# Led_7_dig_display.net
KiCad netlist of a schematic drawn in Altium Designer
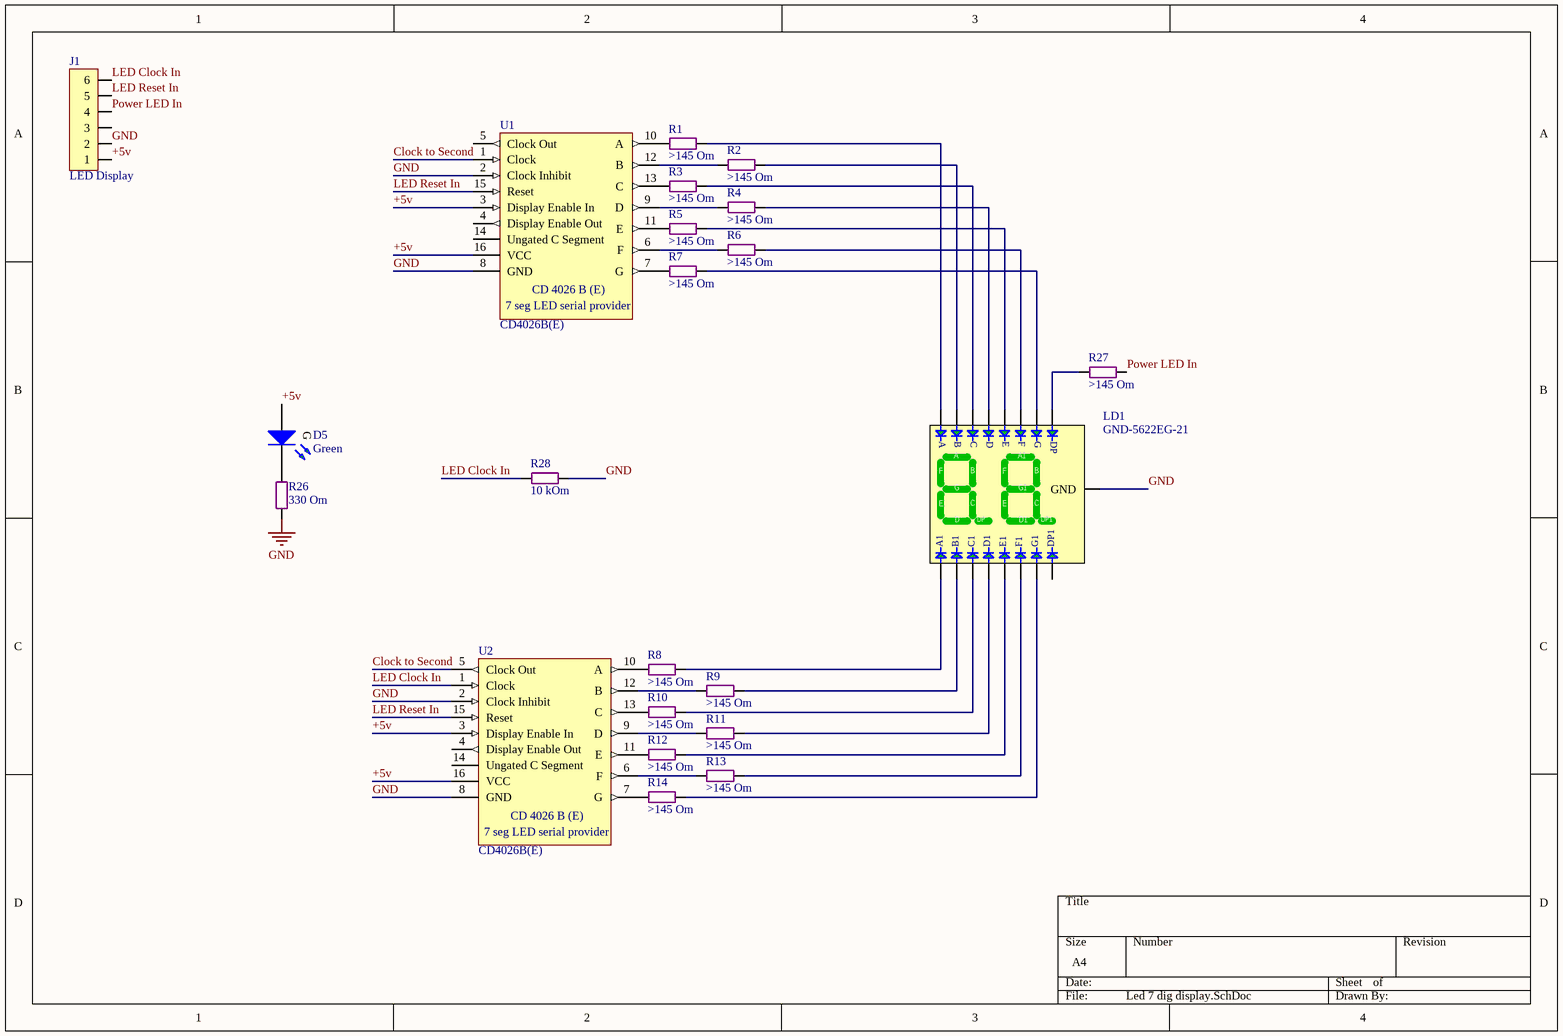
[diagram p0: Led 7 dig display.SchDoc]

(export (version "E")
  (design (tool "Eeschema 10.0.6"))
  (components
    (comp (ref "D5")
      (value "Green")
      (footprint "LED:LED SMD 0805 Green")
      (description "?2v ?20mA")
      (libsource (lib "LED") (part "Led SMD 0805 Green"))
    )
    (comp (ref "J1")
      (value "LED Display")
      (footprint "Connector:Molex Micro-Fit 3.0 - 6 pin D R")
      (description "Horisontal, Dbl line, Male - 3mm")
      (libsource (lib "Connector") (part "Micro-Fit 6R (2x3)"))
    )
    (comp (ref "LD1")
      (value "GND-5622EG-21")
      (footprint "LED:GND-5622EG-21")
      (description "Green, Common Catode 2 Digits")
      (libsource (lib "LED") (part "7 Seg GND-5622EG-21"))
    )
    (comp (ref "R1")
      (value ">145 Om")
      (footprint "PassiveComponents:SMD 1206 (3216)")
      (libsource (lib "PassiveComponents") (part "Res All Types"))
    )
    (comp (ref "R2")
      (value ">145 Om")
      (footprint "PassiveComponents:SMD 1206 (3216)")
      (libsource (lib "PassiveComponents") (part "Res All Types"))
    )
    (comp (ref "R3")
      (value ">145 Om")
      (footprint "PassiveComponents:SMD 1206 (3216)")
      (libsource (lib "PassiveComponents") (part "Res All Types"))
    )
    (comp (ref "R4")
      (value ">145 Om")
      (footprint "PassiveComponents:SMD 1206 (3216)")
      (libsource (lib "PassiveComponents") (part "Res All Types"))
    )
    (comp (ref "R5")
      (value ">145 Om")
      (footprint "PassiveComponents:SMD 1206 (3216)")
      (libsource (lib "PassiveComponents") (part "Res All Types"))
    )
    (comp (ref "R6")
      (value ">145 Om")
      (footprint "PassiveComponents:Res p7.62 (4p) 0.25w")
      (libsource (lib "PassiveComponents") (part "Res All Types"))
    )
    (comp (ref "R7")
      (value ">145 Om")
      (footprint "PassiveComponents:Res p7.62 (4p) 0.25w")
      (libsource (lib "PassiveComponents") (part "Res All Types"))
    )
    (comp (ref "R8")
      (value ">145 Om")
      (footprint "PassiveComponents:SMD 1206 (3216)")
      (libsource (lib "PassiveComponents") (part "Res All Types"))
    )
    (comp (ref "R9")
      (value ">145 Om")
      (footprint "PassiveComponents:Res p7.62 (4p) 0.25w")
      (libsource (lib "PassiveComponents") (part "Res All Types"))
    )
    (comp (ref "R10")
      (value ">145 Om")
      (footprint "PassiveComponents:SMD 1206 (3216)")
      (libsource (lib "PassiveComponents") (part "Res All Types"))
    )
    (comp (ref "R11")
      (value ">145 Om")
      (footprint "PassiveComponents:SMD 1206 (3216)")
      (libsource (lib "PassiveComponents") (part "Res All Types"))
    )
    (comp (ref "R12")
      (value ">145 Om")
      (footprint "PassiveComponents:SMD 1206 (3216)")
      (libsource (lib "PassiveComponents") (part "Res All Types"))
    )
    (comp (ref "R13")
      (value ">145 Om")
      (footprint "PassiveComponents:SMD 1206 (3216)")
      (libsource (lib "PassiveComponents") (part "Res All Types"))
    )
    (comp (ref "R14")
      (value ">145 Om")
      (footprint "PassiveComponents:Res p7.62 (4p) 0.25w")
      (libsource (lib "PassiveComponents") (part "Res All Types"))
    )
    (comp (ref "R26")
      (value "330 Om")
      (footprint "PassiveComponents:SMD 1206 (3216)")
      (libsource (lib "PassiveComponents") (part "Res All Types"))
    )
    (comp (ref "R27")
      (value ">145 Om")
      (footprint "PassiveComponents:SMD 1206 (3216)")
      (libsource (lib "PassiveComponents") (part "Res SMD 1206"))
    )
    (comp (ref "R28")
      (value "10 kOm")
      (footprint "PassiveComponents:SMD 0805 (2012)")
      (libsource (lib "PassiveComponents") (part "Res All Types"))
    )
    (comp (ref "U1")
      (value "CD4026B(E)")
      (footprint "GeneralCases:DIP-16")
      (description "jk Trigger")
      (libsource (lib "Chips") (part "CD4026BE"))
    )
    (comp (ref "U2")
      (value "CD4026B(E)")
      (footprint "GeneralCases:DIP-16")
      (description "jk Trigger")
      (libsource (lib "Chips") (part "CD4026BE"))
    )
  )
  (nets
    (net (code "1") (name "/+5v") (class "Default")
      (node (ref "D5") (pin "A") (pinfunction "A_A") (pintype "passive"))
      (node (ref "J1") (pin "1") (pinfunction "1_1") (pintype "passive"))
      (node (ref "U1") (pin "16") (pinfunction "VCC_16") (pintype "power_in"))
      (node (ref "U1") (pin "3") (pinfunction "Display_Enable_In_3") (pintype "input"))
      (node (ref "U2") (pin "16") (pinfunction "VCC_16") (pintype "power_in"))
      (node (ref "U2") (pin "3") (pinfunction "Display_Enable_In_3") (pintype "input"))
    )
    (net (code "2") (name "/Clock to Second") (class "Default")
      (node (ref "U1") (pin "1") (pinfunction "Clock_1") (pintype "input"))
      (node (ref "U2") (pin "5") (pinfunction "Clock_Out_5") (pintype "output"))
    )
    (net (code "3") (name "/LED Clock In") (class "Default")
      (node (ref "J1") (pin "6") (pinfunction "6_6") (pintype "passive"))
      (node (ref "R28") (pin "1") (pinfunction "1_1") (pintype "passive"))
      (node (ref "U2") (pin "1") (pinfunction "Clock_1") (pintype "input"))
    )
    (net (code "4") (name "/LED Reset In") (class "Default")
      (node (ref "J1") (pin "5") (pinfunction "5_5") (pintype "passive"))
      (node (ref "U1") (pin "15") (pinfunction "Reset_15") (pintype "input"))
      (node (ref "U2") (pin "15") (pinfunction "Reset_15") (pintype "input"))
    )
    (net (code "5") (name "/Power LED In") (class "Default")
      (node (ref "J1") (pin "4") (pinfunction "4_4") (pintype "passive"))
      (node (ref "R27") (pin "2") (pinfunction "2_2") (pintype "passive"))
    )
    (net (code "6") (name "GND") (class "Default")
      (node (ref "J1") (pin "2") (pinfunction "2_2") (pintype "passive"))
      (node (ref "LD1") (pin "GND") (pinfunction "GND_GND") (pintype "passive"))
      (node (ref "R26") (pin "2") (pinfunction "2_2") (pintype "passive"))
      (node (ref "R28") (pin "2") (pinfunction "2_2") (pintype "passive"))
      (node (ref "U1") (pin "2") (pinfunction "Clock_Inhibit_2") (pintype "input"))
      (node (ref "U1") (pin "8") (pinfunction "GND_8") (pintype "power_in"))
      (node (ref "U2") (pin "2") (pinfunction "Clock_Inhibit_2") (pintype "input"))
      (node (ref "U2") (pin "8") (pinfunction "GND_8") (pintype "power_in"))
    )
    (net (code "7") (name "Net-(D5-PadK)") (class "Default")
      (node (ref "D5") (pin "K") (pinfunction "K_K") (pintype "passive"))
      (node (ref "R26") (pin "1") (pinfunction "1_1") (pintype "passive"))
    )
    (net (code "8") (name "Net-(LD1-PadA)") (class "Default")
      (node (ref "LD1") (pin "A") (pinfunction "A_A") (pintype "passive"))
      (node (ref "R1") (pin "2") (pinfunction "2_2") (pintype "passive"))
    )
    (net (code "9") (name "Net-(LD1-PadA1)") (class "Default")
      (node (ref "LD1") (pin "A1") (pinfunction "A1_A1") (pintype "passive"))
      (node (ref "R8") (pin "2") (pinfunction "2_2") (pintype "passive"))
    )
    (net (code "10") (name "Net-(LD1-PadB)") (class "Default")
      (node (ref "LD1") (pin "B") (pinfunction "B_B") (pintype "passive"))
      (node (ref "R2") (pin "2") (pinfunction "2_2") (pintype "passive"))
    )
    (net (code "11") (name "Net-(LD1-PadB1)") (class "Default")
      (node (ref "LD1") (pin "B1") (pinfunction "B1_B1") (pintype "passive"))
      (node (ref "R9") (pin "2") (pinfunction "2_2") (pintype "passive"))
    )
    (net (code "12") (name "Net-(LD1-PadC)") (class "Default")
      (node (ref "LD1") (pin "C") (pinfunction "C_C") (pintype "passive"))
      (node (ref "R3") (pin "2") (pinfunction "2_2") (pintype "passive"))
    )
    (net (code "13") (name "Net-(LD1-PadC1)") (class "Default")
      (node (ref "LD1") (pin "C1") (pinfunction "C1_C1") (pintype "passive"))
      (node (ref "R10") (pin "2") (pinfunction "2_2") (pintype "passive"))
    )
    (net (code "14") (name "Net-(LD1-PadD)") (class "Default")
      (node (ref "LD1") (pin "D") (pinfunction "D_D") (pintype "passive"))
      (node (ref "R4") (pin "2") (pinfunction "2_2") (pintype "passive"))
    )
    (net (code "15") (name "Net-(LD1-PadD1)") (class "Default")
      (node (ref "LD1") (pin "D1") (pinfunction "D1_D1") (pintype "passive"))
      (node (ref "R11") (pin "2") (pinfunction "2_2") (pintype "passive"))
    )
    (net (code "16") (name "Net-(LD1-PadDP)") (class "Default")
      (node (ref "LD1") (pin "DP") (pinfunction "DP_DP") (pintype "passive"))
      (node (ref "R27") (pin "1") (pinfunction "1_1") (pintype "passive"))
    )
    (net (code "17") (name "Net-(LD1-PadE)") (class "Default")
      (node (ref "LD1") (pin "E") (pinfunction "E_E") (pintype "passive"))
      (node (ref "R5") (pin "2") (pinfunction "2_2") (pintype "passive"))
    )
    (net (code "18") (name "Net-(LD1-PadE1)") (class "Default")
      (node (ref "LD1") (pin "E1") (pinfunction "E1_E1") (pintype "passive"))
      (node (ref "R12") (pin "2") (pinfunction "2_2") (pintype "passive"))
    )
    (net (code "19") (name "Net-(LD1-PadF)") (class "Default")
      (node (ref "LD1") (pin "F") (pinfunction "F_F") (pintype "passive"))
      (node (ref "R6") (pin "2") (pinfunction "2_2") (pintype "passive"))
    )
    (net (code "20") (name "Net-(LD1-PadF1)") (class "Default")
      (node (ref "LD1") (pin "F1") (pinfunction "F1_F1") (pintype "passive"))
      (node (ref "R13") (pin "2") (pinfunction "2_2") (pintype "passive"))
    )
    (net (code "21") (name "Net-(LD1-PadG)") (class "Default")
      (node (ref "LD1") (pin "G") (pinfunction "G_G") (pintype "passive"))
      (node (ref "R7") (pin "2") (pinfunction "2_2") (pintype "passive"))
    )
    (net (code "22") (name "Net-(LD1-PadG1)") (class "Default")
      (node (ref "LD1") (pin "G1") (pinfunction "G1_G1") (pintype "passive"))
      (node (ref "R14") (pin "2") (pinfunction "2_2") (pintype "passive"))
    )
    (net (code "23") (name "Net-(U1-A)") (class "Default")
      (node (ref "R1") (pin "1") (pinfunction "1_1") (pintype "passive"))
      (node (ref "U1") (pin "10") (pinfunction "A_10") (pintype "output"))
    )
    (net (code "24") (name "Net-(U1-B)") (class "Default")
      (node (ref "R2") (pin "1") (pinfunction "1_1") (pintype "passive"))
      (node (ref "U1") (pin "12") (pinfunction "B_12") (pintype "output"))
    )
    (net (code "25") (name "Net-(U1-C)") (class "Default")
      (node (ref "R3") (pin "1") (pinfunction "1_1") (pintype "passive"))
      (node (ref "U1") (pin "13") (pinfunction "C_13") (pintype "output"))
    )
    (net (code "26") (name "Net-(U1-D)") (class "Default")
      (node (ref "R4") (pin "1") (pinfunction "1_1") (pintype "passive"))
      (node (ref "U1") (pin "9") (pinfunction "D_9") (pintype "output"))
    )
    (net (code "27") (name "Net-(U1-E)") (class "Default")
      (node (ref "R5") (pin "1") (pinfunction "1_1") (pintype "passive"))
      (node (ref "U1") (pin "11") (pinfunction "E_11") (pintype "output"))
    )
    (net (code "28") (name "Net-(U1-F)") (class "Default")
      (node (ref "R6") (pin "1") (pinfunction "1_1") (pintype "passive"))
      (node (ref "U1") (pin "6") (pinfunction "F_6") (pintype "output"))
    )
    (net (code "29") (name "Net-(U1-G)") (class "Default")
      (node (ref "R7") (pin "1") (pinfunction "1_1") (pintype "passive"))
      (node (ref "U1") (pin "7") (pinfunction "G_7") (pintype "output"))
    )
    (net (code "30") (name "Net-(U2-A)") (class "Default")
      (node (ref "R8") (pin "1") (pinfunction "1_1") (pintype "passive"))
      (node (ref "U2") (pin "10") (pinfunction "A_10") (pintype "output"))
    )
    (net (code "31") (name "Net-(U2-B)") (class "Default")
      (node (ref "R9") (pin "1") (pinfunction "1_1") (pintype "passive"))
      (node (ref "U2") (pin "12") (pinfunction "B_12") (pintype "output"))
    )
    (net (code "32") (name "Net-(U2-C)") (class "Default")
      (node (ref "R10") (pin "1") (pinfunction "1_1") (pintype "passive"))
      (node (ref "U2") (pin "13") (pinfunction "C_13") (pintype "output"))
    )
    (net (code "33") (name "Net-(U2-D)") (class "Default")
      (node (ref "R11") (pin "1") (pinfunction "1_1") (pintype "passive"))
      (node (ref "U2") (pin "9") (pinfunction "D_9") (pintype "output"))
    )
    (net (code "34") (name "Net-(U2-E)") (class "Default")
      (node (ref "R12") (pin "1") (pinfunction "1_1") (pintype "passive"))
      (node (ref "U2") (pin "11") (pinfunction "E_11") (pintype "output"))
    )
    (net (code "35") (name "Net-(U2-F)") (class "Default")
      (node (ref "R13") (pin "1") (pinfunction "1_1") (pintype "passive"))
      (node (ref "U2") (pin "6") (pinfunction "F_6") (pintype "output"))
    )
    (net (code "36") (name "Net-(U2-G)") (class "Default")
      (node (ref "R14") (pin "1") (pinfunction "1_1") (pintype "passive"))
      (node (ref "U2") (pin "7") (pinfunction "G_7") (pintype "output"))
    )
    (net (code "37") (name "unconnected-(J1-Pad3)") (class "Default")
      (node (ref "J1") (pin "3") (pinfunction "3_3") (pintype "passive"))
    )
    (net (code "38") (name "unconnected-(LD1-PadDP1)") (class "Default")
      (node (ref "LD1") (pin "DP1") (pinfunction "DP1_DP1") (pintype "passive"))
    )
    (net (code "39") (name "unconnected-(U1-Clock_Out-Pad5)") (class "Default")
      (node (ref "U1") (pin "5") (pinfunction "Clock_Out_5") (pintype "output"))
    )
    (net (code "40") (name "unconnected-(U1-Display_Enable_Out-Pad4)") (class "Default")
      (node (ref "U1") (pin "4") (pinfunction "Display_Enable_Out_4") (pintype "output"))
    )
    (net (code "41") (name "unconnected-(U1-Ungated_C_Segment-Pad14)") (class "Default")
      (node (ref "U1") (pin "14") (pinfunction "Ungated_C_Segment_14") (pintype "passive"))
    )
    (net (code "42") (name "unconnected-(U2-Display_Enable_Out-Pad4)") (class "Default")
      (node (ref "U2") (pin "4") (pinfunction "Display_Enable_Out_4") (pintype "output"))
    )
    (net (code "43") (name "unconnected-(U2-Ungated_C_Segment-Pad14)") (class "Default")
      (node (ref "U2") (pin "14") (pinfunction "Ungated_C_Segment_14") (pintype "passive"))
    )
  )
)
